# Logic_IO_Protection.net
KiCad netlist of a schematic drawn in Altium Designer
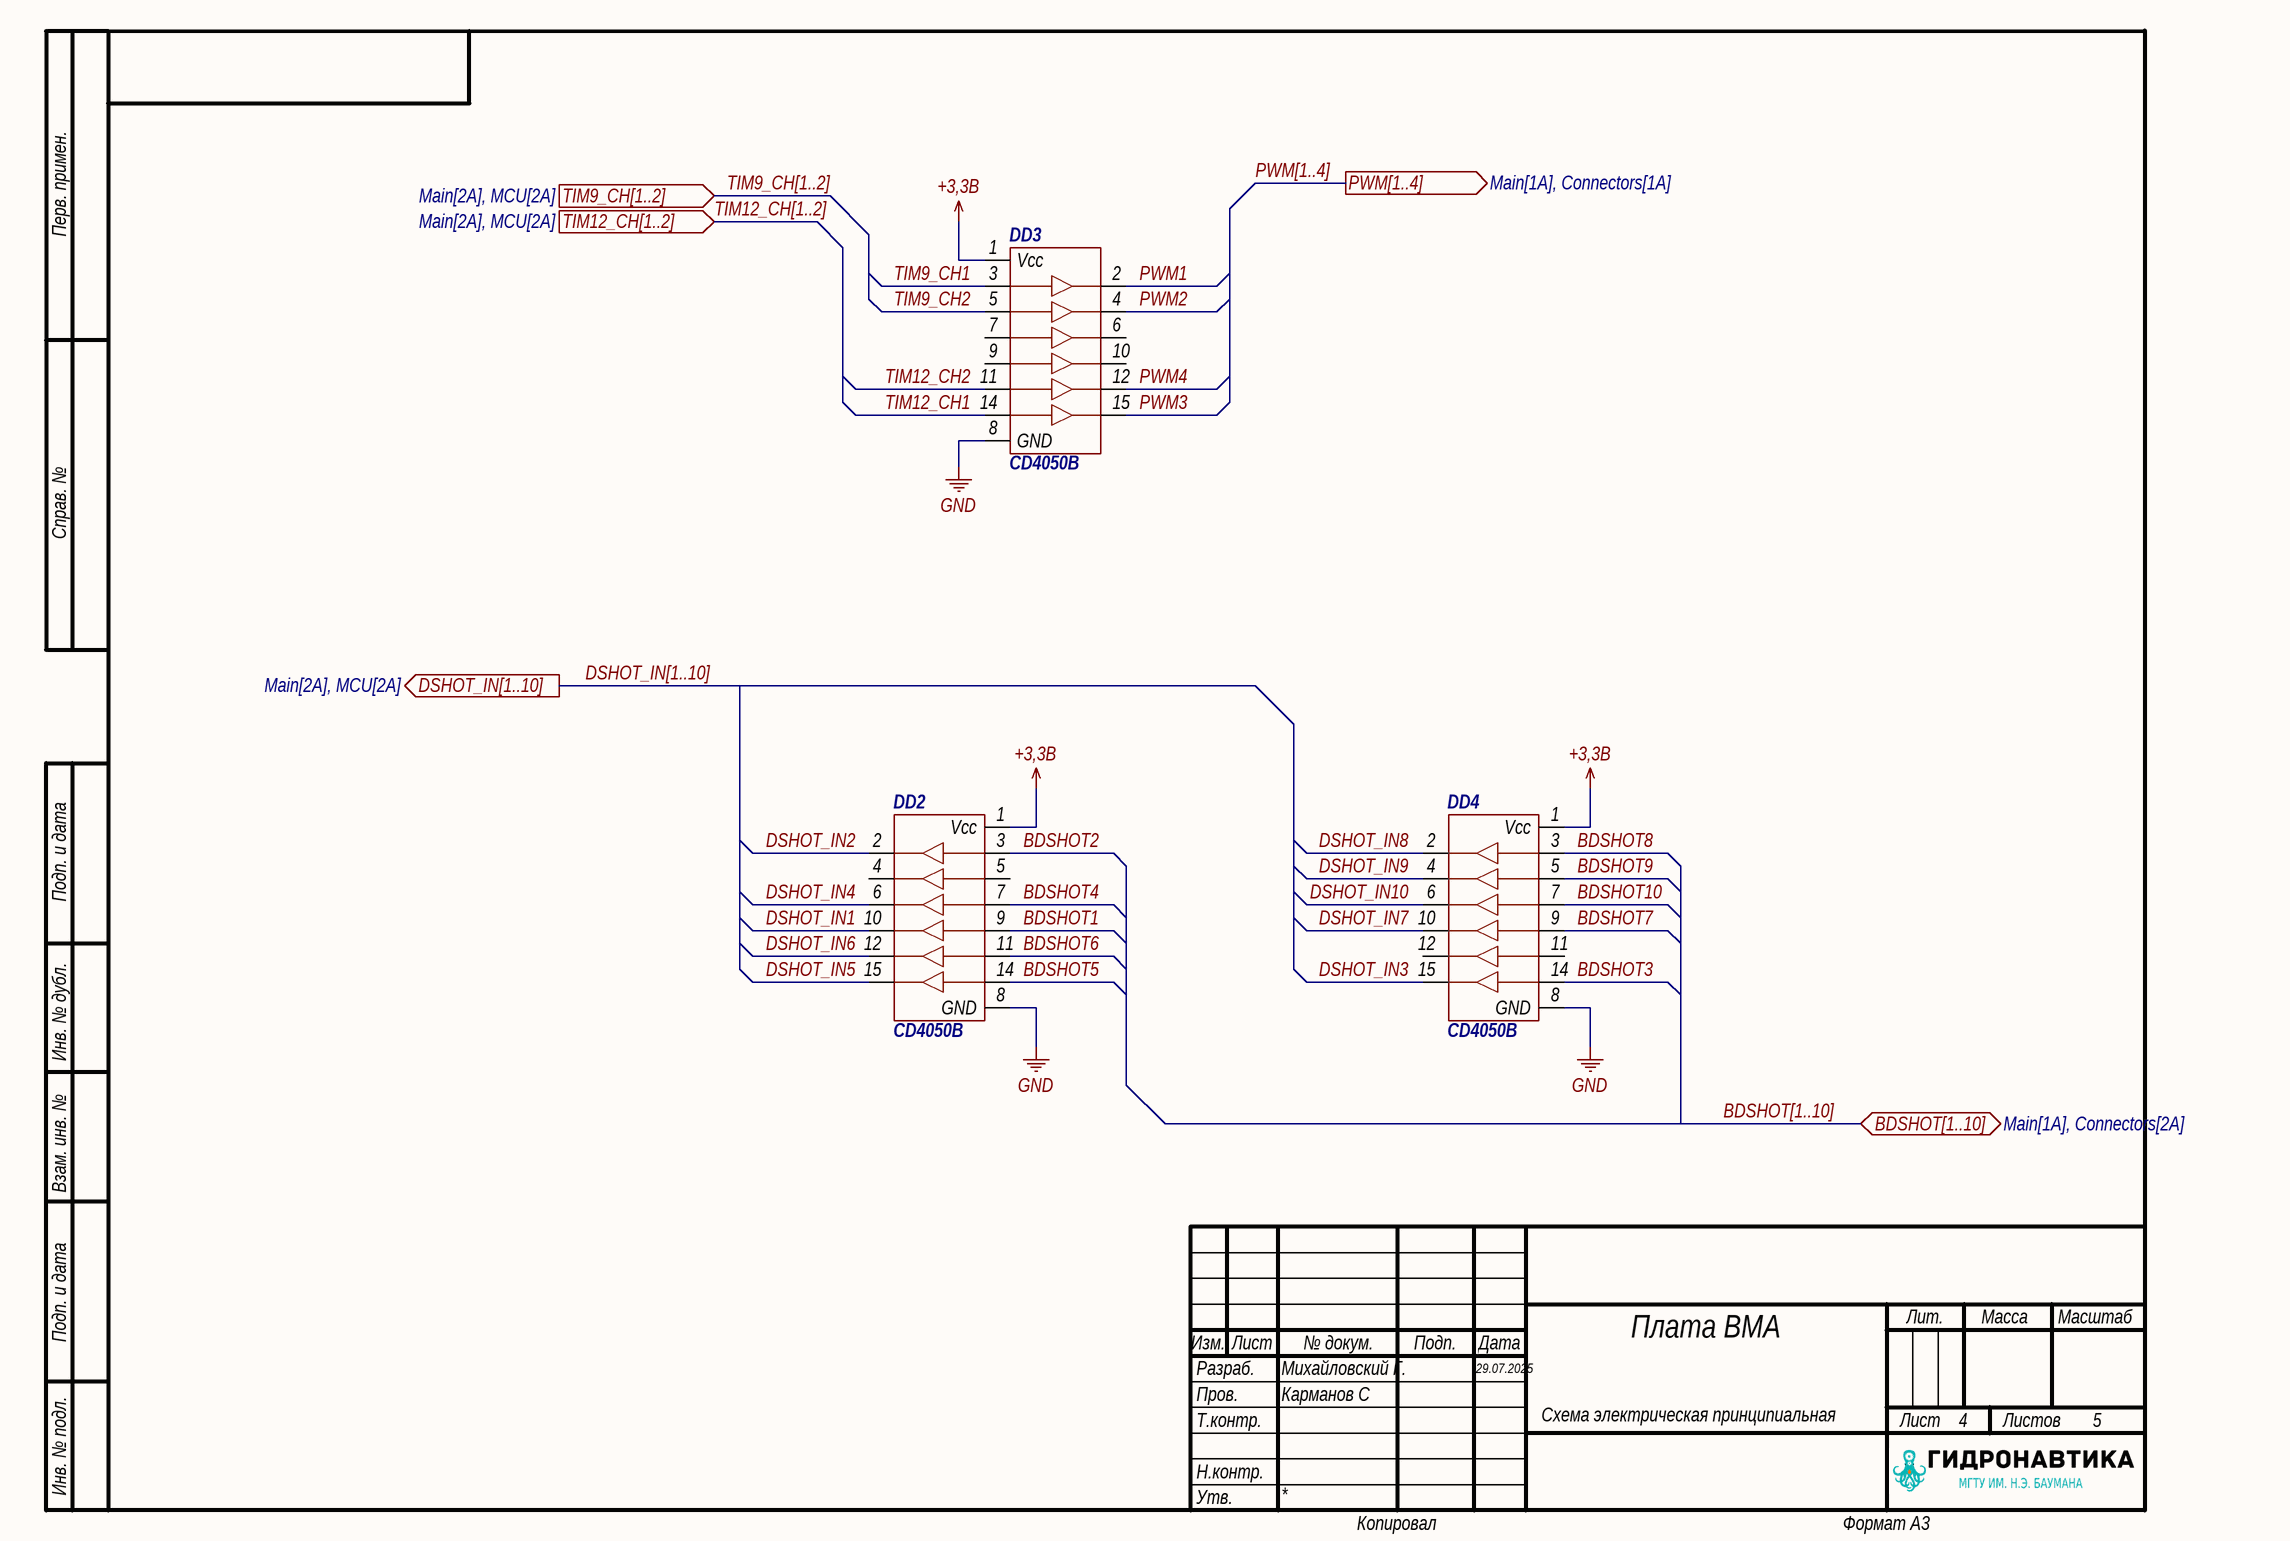
[diagram p0: Logic_IO_Protection.SchDoc]

(export (version "E")
  (design (tool "Eeschema 10.0.6"))
  (components
    (comp (ref "DD2")
      (value "CD4050B")
      (footprint "SOIC-16")
      (description "Шесть буферных элементов")
      (libsource (lib "Hydrolib") (part "CD4050B"))
    )
    (comp (ref "DD3")
      (value "CD4050B")
      (footprint "SOIC-16")
      (description "Шесть буферных элементов")
      (libsource (lib "") (part "CD4050B_1"))
    )
    (comp (ref "DD4")
      (value "CD4050B")
      (footprint "SOIC-16")
      (description "Шесть буферных элементов")
      (libsource (lib "Hydrolib") (part "CD4050B"))
    )
  )
  (nets
    (net (code "1") (name "+3,3В") (class "Default")
      (node (ref "DD2") (pin "1") (pinfunction "Vcc_1") (pintype "passive"))
      (node (ref "DD3") (pin "1") (pinfunction "Vcc_1") (pintype "passive"))
      (node (ref "DD4") (pin "1") (pinfunction "Vcc_1") (pintype "passive"))
    )
    (net (code "2") (name "/BDSHOT1") (class "Default")
      (node (ref "DD2") (pin "9") (pinfunction "A4_9") (pintype "passive"))
    )
    (net (code "3") (name "/BDSHOT2") (class "Default")
      (node (ref "DD2") (pin "3") (pinfunction "A1_3") (pintype "passive"))
    )
    (net (code "4") (name "/BDSHOT3") (class "Default")
      (node (ref "DD4") (pin "14") (pinfunction "A6_14") (pintype "passive"))
    )
    (net (code "5") (name "/BDSHOT4") (class "Default")
      (node (ref "DD2") (pin "7") (pinfunction "A3_7") (pintype "passive"))
    )
    (net (code "6") (name "/BDSHOT5") (class "Default")
      (node (ref "DD2") (pin "14") (pinfunction "A6_14") (pintype "passive"))
    )
    (net (code "7") (name "/BDSHOT6") (class "Default")
      (node (ref "DD2") (pin "11") (pinfunction "A5_11") (pintype "passive"))
    )
    (net (code "8") (name "/BDSHOT7") (class "Default")
      (node (ref "DD4") (pin "9") (pinfunction "A4_9") (pintype "passive"))
    )
    (net (code "9") (name "/BDSHOT8") (class "Default")
      (node (ref "DD4") (pin "3") (pinfunction "A1_3") (pintype "passive"))
    )
    (net (code "10") (name "/BDSHOT9") (class "Default")
      (node (ref "DD4") (pin "5") (pinfunction "A2_5") (pintype "passive"))
    )
    (net (code "11") (name "/BDSHOT10") (class "Default")
      (node (ref "DD4") (pin "7") (pinfunction "A3_7") (pintype "passive"))
    )
    (net (code "13") (name "/DSHOT_IN1") (class "Default")
      (node (ref "DD2") (pin "10") (pinfunction "Y10_10") (pintype "passive"))
    )
    (net (code "14") (name "/DSHOT_IN2") (class "Default")
      (node (ref "DD2") (pin "2") (pinfunction "Y1_2") (pintype "passive"))
    )
    (net (code "15") (name "/DSHOT_IN3") (class "Default")
      (node (ref "DD4") (pin "15") (pinfunction "Y6_15") (pintype "passive"))
    )
    (net (code "16") (name "/DSHOT_IN4") (class "Default")
      (node (ref "DD2") (pin "6") (pinfunction "Y3_6") (pintype "passive"))
    )
    (net (code "17") (name "/DSHOT_IN5") (class "Default")
      (node (ref "DD2") (pin "15") (pinfunction "Y6_15") (pintype "passive"))
    )
    (net (code "18") (name "/DSHOT_IN6") (class "Default")
      (node (ref "DD2") (pin "12") (pinfunction "Y5_12") (pintype "passive"))
    )
    (net (code "19") (name "/DSHOT_IN7") (class "Default")
      (node (ref "DD4") (pin "10") (pinfunction "Y10_10") (pintype "passive"))
    )
    (net (code "20") (name "/DSHOT_IN8") (class "Default")
      (node (ref "DD4") (pin "2") (pinfunction "Y1_2") (pintype "passive"))
    )
    (net (code "21") (name "/DSHOT_IN9") (class "Default")
      (node (ref "DD4") (pin "4") (pinfunction "Y2_4") (pintype "passive"))
    )
    (net (code "22") (name "/DSHOT_IN10") (class "Default")
      (node (ref "DD4") (pin "6") (pinfunction "Y3_6") (pintype "passive"))
    )
    (net (code "24") (name "/PWM1") (class "Default")
      (node (ref "DD3") (pin "2") (pinfunction "Y1_2") (pintype "passive"))
    )
    (net (code "25") (name "/PWM2") (class "Default")
      (node (ref "DD3") (pin "4") (pinfunction "Y2_4") (pintype "passive"))
    )
    (net (code "26") (name "/PWM3") (class "Default")
      (node (ref "DD3") (pin "15") (pinfunction "Y6_15") (pintype "passive"))
    )
    (net (code "27") (name "/PWM4") (class "Default")
      (node (ref "DD3") (pin "12") (pinfunction "Y5_12") (pintype "passive"))
    )
    (net (code "29") (name "/TIM9_CH1") (class "Default")
      (node (ref "DD3") (pin "3") (pinfunction "A1_3") (pintype "passive"))
    )
    (net (code "30") (name "/TIM9_CH2") (class "Default")
      (node (ref "DD3") (pin "5") (pinfunction "A2_5") (pintype "passive"))
    )
    (net (code "32") (name "/TIM12_CH1") (class "Default")
      (node (ref "DD3") (pin "14") (pinfunction "A6_14") (pintype "passive"))
    )
    (net (code "33") (name "/TIM12_CH2") (class "Default")
      (node (ref "DD3") (pin "11") (pinfunction "A5_11") (pintype "passive"))
    )
    (net (code "35") (name "GND") (class "Default")
      (node (ref "DD2") (pin "8") (pinfunction "GND_8") (pintype "passive"))
      (node (ref "DD3") (pin "8") (pinfunction "GND_8") (pintype "passive"))
      (node (ref "DD4") (pin "8") (pinfunction "GND_8") (pintype "passive"))
    )
    (net (code "36") (name "unconnected-(DD2-A2-Pad5)") (class "Default")
      (node (ref "DD2") (pin "5") (pinfunction "A2_5") (pintype "passive"))
    )
    (net (code "37") (name "unconnected-(DD2-Y2-Pad4)") (class "Default")
      (node (ref "DD2") (pin "4") (pinfunction "Y2_4") (pintype "passive"))
    )
    (net (code "38") (name "unconnected-(DD3-A3-Pad7)") (class "Default")
      (node (ref "DD3") (pin "7") (pinfunction "A3_7") (pintype "passive"))
    )
    (net (code "39") (name "unconnected-(DD3-A4-Pad9)") (class "Default")
      (node (ref "DD3") (pin "9") (pinfunction "A4_9") (pintype "passive"))
    )
    (net (code "40") (name "unconnected-(DD3-Y3-Pad6)") (class "Default")
      (node (ref "DD3") (pin "6") (pinfunction "Y3_6") (pintype "passive"))
    )
    (net (code "41") (name "unconnected-(DD3-Y10-Pad10)") (class "Default")
      (node (ref "DD3") (pin "10") (pinfunction "Y10_10") (pintype "passive"))
    )
    (net (code "42") (name "unconnected-(DD4-A5-Pad11)") (class "Default")
      (node (ref "DD4") (pin "11") (pinfunction "A5_11") (pintype "passive"))
    )
    (net (code "43") (name "unconnected-(DD4-Y5-Pad12)") (class "Default")
      (node (ref "DD4") (pin "12") (pinfunction "Y5_12") (pintype "passive"))
    )
  )
)
